# UVBoxSchematic_r.net
KiCad netlist of a schematic drawn in EAGLE
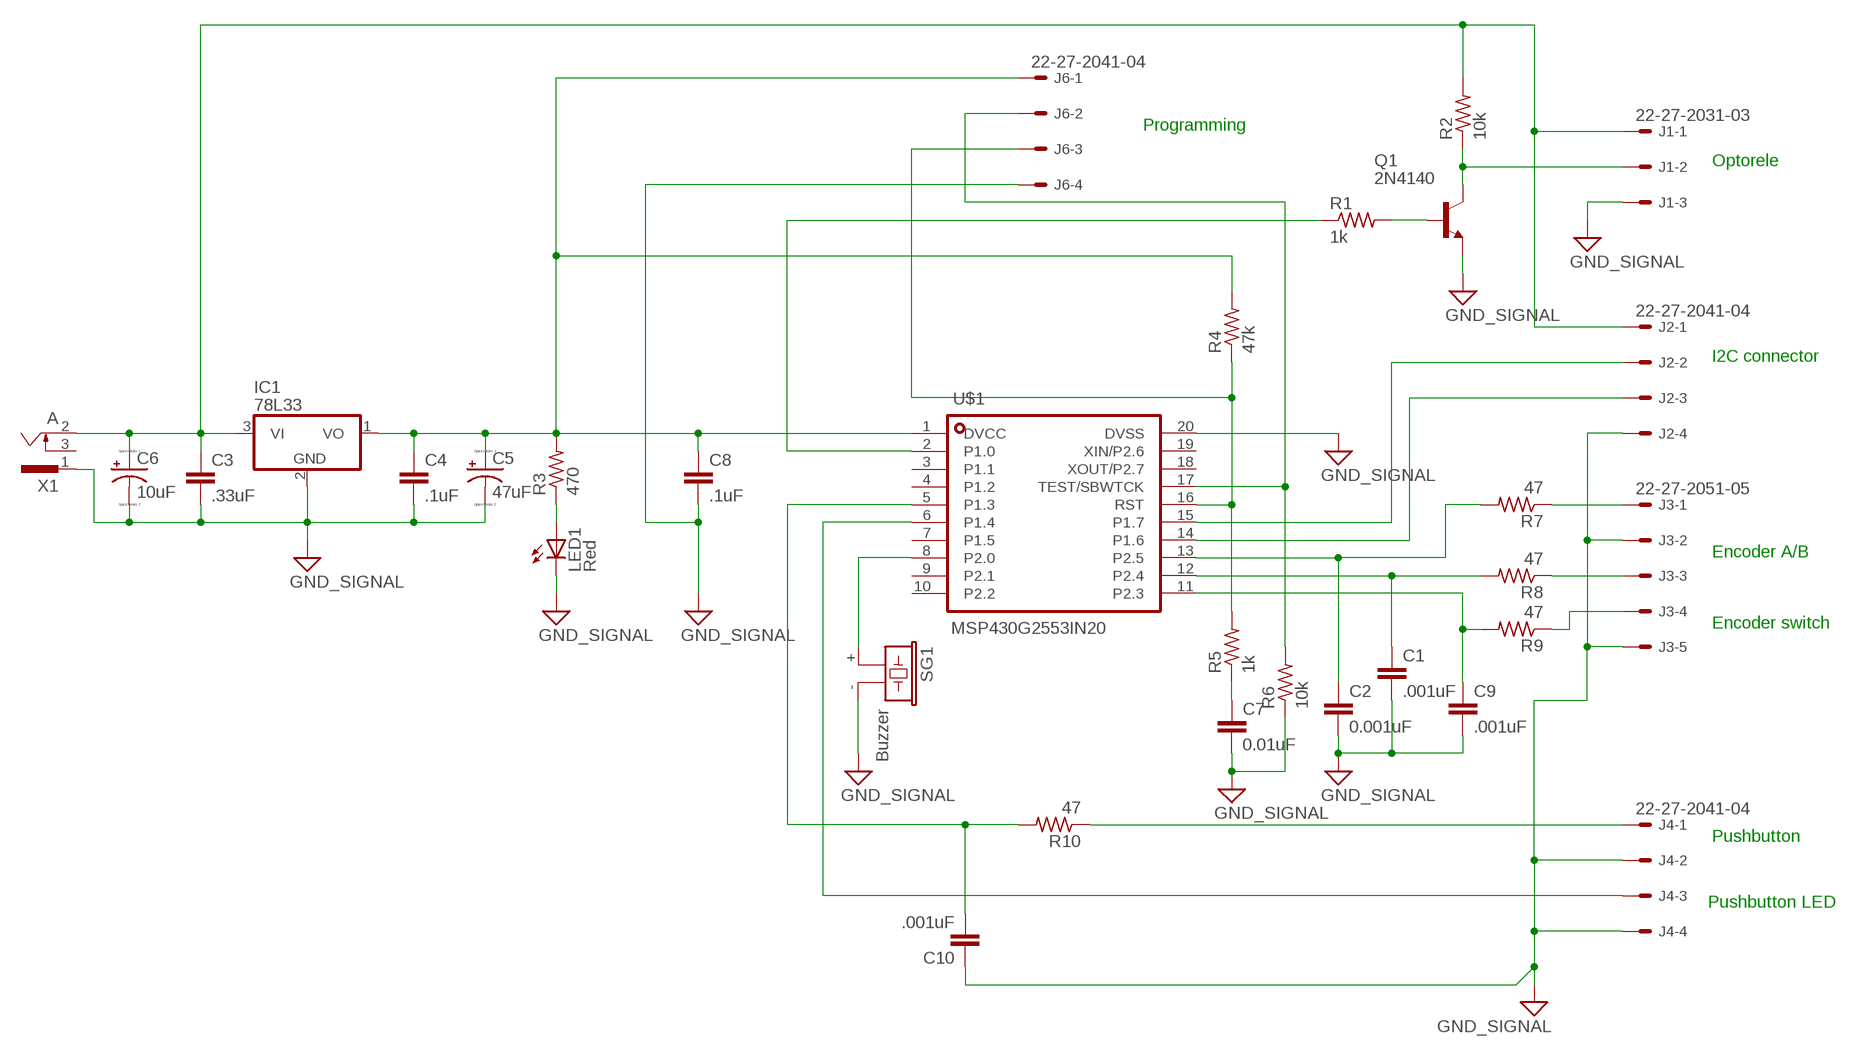
[diagram p0: schematic, sheet 1]

(export (version "E")
  (design (tool "Eeschema 10.0.6"))
  (components
    (comp (ref "C1")
      (value ".001uF")
      (footprint "eagle-import:C2.5-2")
      (libsource (lib "eagle-import") (part "C2.5/2"))
    )
    (comp (ref "C2")
      (value "0.001uF")
      (footprint "eagle-import:C2.5-2")
      (libsource (lib "eagle-import") (part "C2.5/2"))
    )
    (comp (ref "C3")
      (value ".33uF")
      (footprint "eagle-import:C2.5-2")
      (libsource (lib "eagle-import") (part "C2.5/2"))
    )
    (comp (ref "C4")
      (value ".1uF")
      (footprint "eagle-import:C2.5-2")
      (libsource (lib "eagle-import") (part "C2.5/2"))
    )
    (comp (ref "C5")
      (value "47uF")
      (footprint "eagle-import:B45181A")
      (libsource (lib "eagle-import") (part "CPOL-USB45181A"))
    )
    (comp (ref "C6")
      (value "10uF")
      (footprint "eagle-import:B45181A")
      (libsource (lib "eagle-import") (part "CPOL-USB45181A"))
    )
    (comp (ref "C7")
      (value "0.01uF")
      (footprint "eagle-import:C2.5-2")
      (libsource (lib "eagle-import") (part "C2.5/2"))
    )
    (comp (ref "C8")
      (value ".1uF")
      (footprint "eagle-import:C2.5-2")
      (libsource (lib "eagle-import") (part "C2.5/2"))
    )
    (comp (ref "C9")
      (value ".001uF")
      (footprint "eagle-import:C2.5-2")
      (libsource (lib "eagle-import") (part "C2.5/2"))
    )
    (comp (ref "C10")
      (value ".001uF")
      (footprint "eagle-import:C2.5-2")
      (libsource (lib "eagle-import") (part "C2.5/2"))
    )
    (comp (ref "IC1")
      (value "78L33")
      (footprint "eagle-import:TO92")
      (libsource (lib "eagle-import") (part "78ZL05"))
    )
    (comp (ref "J1")
      (value "22-27-2031-03")
      (footprint "eagle-import:6410-03")
      (libsource (lib "eagle-import") (part "22-?-0327-2031"))
    )
    (comp (ref "J2")
      (value "22-27-2041-04")
      (footprint "eagle-import:6410-04")
      (libsource (lib "eagle-import") (part "22-?-0427-2041"))
    )
    (comp (ref "J3")
      (value "22-27-2051-05")
      (footprint "eagle-import:6410-05")
      (libsource (lib "eagle-import") (part "22-?-0527-2051"))
    )
    (comp (ref "J4")
      (value "22-27-2041-04")
      (footprint "eagle-import:6410-04")
      (libsource (lib "eagle-import") (part "22-?-0427-2041"))
    )
    (comp (ref "J6")
      (value "22-27-2041-04")
      (footprint "eagle-import:6410-04")
      (libsource (lib "eagle-import") (part "22-?-0427-2041"))
    )
    (comp (ref "LED1")
      (value "Red")
      (footprint "eagle-import:LED3MM")
      (libsource (lib "eagle-import") (part "LED3MM"))
    )
    (comp (ref "Q1")
      (value "2N4140")
      (footprint "eagle-import:TO18")
      (libsource (lib "eagle-import") (part "2N4104"))
    )
    (comp (ref "R1")
      (value "1k")
      (footprint "eagle-import:0204_7")
      (libsource (lib "eagle-import") (part "R-US_0204/7"))
    )
    (comp (ref "R2")
      (value "10k")
      (footprint "eagle-import:0204_7")
      (libsource (lib "eagle-import") (part "R-US_0204/7"))
    )
    (comp (ref "R3")
      (value "470")
      (footprint "eagle-import:0204_7")
      (libsource (lib "eagle-import") (part "R-US_0204/7"))
    )
    (comp (ref "R4")
      (value "47k")
      (footprint "eagle-import:0204_7")
      (libsource (lib "eagle-import") (part "R-US_0204/7"))
    )
    (comp (ref "R5")
      (value "1k")
      (footprint "eagle-import:0204_7")
      (libsource (lib "eagle-import") (part "R-US_0204/7"))
    )
    (comp (ref "R6")
      (value "10k")
      (footprint "eagle-import:0204_7")
      (libsource (lib "eagle-import") (part "R-US_0204/7"))
    )
    (comp (ref "R7")
      (value "47")
      (footprint "eagle-import:0204_7")
      (libsource (lib "eagle-import") (part "R-US_0204/7"))
    )
    (comp (ref "R8")
      (value "47")
      (footprint "eagle-import:0204_7")
      (libsource (lib "eagle-import") (part "R-US_0204/7"))
    )
    (comp (ref "R9")
      (value "47")
      (footprint "eagle-import:0204_7")
      (libsource (lib "eagle-import") (part "R-US_0204/7"))
    )
    (comp (ref "R10")
      (value "47")
      (footprint "eagle-import:0204_7")
      (libsource (lib "eagle-import") (part "R-US_0204/7"))
    )
    (comp (ref "SG1")
      (value "Buzzer")
      (footprint "eagle-import:F_CM04P")
      (libsource (lib "eagle-import") (part "F/CM04P"))
    )
    (comp (ref "U$1")
      (value "MSP430G2553IN20")
      (footprint "eagle-import:DIP20")
      (libsource (lib "eagle-import") (part "MSP430G2553IN20"))
    )
    (comp (ref "X1")
      (value "A")
      (footprint "eagle-import:SCD-014-A")
      (libsource (lib "eagle-import") (part "SCD-014A"))
    )
  )
  (nets
    (net (code "1") (name "GND_SIGNAL") (class "Default")
      (node (ref "C1") (pin "2") (pinfunction "2_2") (pintype "passive"))
      (node (ref "C10") (pin "1") (pinfunction "1_1") (pintype "passive"))
      (node (ref "C2") (pin "2") (pinfunction "2_2") (pintype "passive"))
      (node (ref "C3") (pin "2") (pinfunction "2_2") (pintype "passive"))
      (node (ref "C4") (pin "2") (pinfunction "2_2") (pintype "passive"))
      (node (ref "C5") (pin "-") (pinfunction "-_-") (pintype "passive"))
      (node (ref "C6") (pin "-") (pinfunction "-_-") (pintype "passive"))
      (node (ref "C7") (pin "2") (pinfunction "2_2") (pintype "passive"))
      (node (ref "C8") (pin "2") (pinfunction "2_2") (pintype "passive"))
      (node (ref "C9") (pin "2") (pinfunction "2_2") (pintype "passive"))
      (node (ref "IC1") (pin "2") (pinfunction "GND_2") (pintype "passive"))
      (node (ref "J1") (pin "3") (pinfunction "S_3") (pintype "passive"))
      (node (ref "J2") (pin "4") (pinfunction "S_4") (pintype "passive"))
      (node (ref "J3") (pin "2") (pinfunction "S_2") (pintype "passive"))
      (node (ref "J3") (pin "5") (pinfunction "S_5") (pintype "passive"))
      (node (ref "J4") (pin "2") (pinfunction "S_2") (pintype "passive"))
      (node (ref "J4") (pin "4") (pinfunction "S_4") (pintype "passive"))
      (node (ref "J6") (pin "4") (pinfunction "S_4") (pintype "passive"))
      (node (ref "LED1") (pin "K") (pinfunction "C_K") (pintype "passive"))
      (node (ref "Q1") (pin "1") (pinfunction "E_1") (pintype "passive"))
      (node (ref "R6") (pin "1") (pinfunction "1_1") (pintype "passive"))
      (node (ref "SG1") (pin "-") (pinfunction "2_-") (pintype "passive"))
      (node (ref "U$1") (pin "20") (pinfunction "DVSS_20") (pintype "power_in"))
      (node (ref "X1") (pin "1") (pinfunction "1_1") (pintype "passive"))
    )
    (net (code "2") (name "Net-(C7-Pad1)") (class "Default")
      (node (ref "C7") (pin "1") (pinfunction "1_1") (pintype "passive"))
      (node (ref "R5") (pin "1") (pinfunction "1_1") (pintype "passive"))
    )
    (net (code "3") (name "Net-(IC1-VI)") (class "Default")
      (node (ref "C3") (pin "1") (pinfunction "1_1") (pintype "passive"))
      (node (ref "C6") (pin "+") (pinfunction "+_+") (pintype "passive"))
      (node (ref "IC1") (pin "3") (pinfunction "VI_3") (pintype "input"))
      (node (ref "J1") (pin "1") (pinfunction "S_1") (pintype "passive"))
      (node (ref "J2") (pin "1") (pinfunction "S_1") (pintype "passive"))
      (node (ref "R2") (pin "2") (pinfunction "2_2") (pintype "passive"))
      (node (ref "X1") (pin "2") (pinfunction "2_2") (pintype "passive"))
    )
    (net (code "4") (name "Net-(IC1-VO)") (class "Default")
      (node (ref "C4") (pin "1") (pinfunction "1_1") (pintype "passive"))
      (node (ref "C5") (pin "+") (pinfunction "+_+") (pintype "passive"))
      (node (ref "C8") (pin "1") (pinfunction "1_1") (pintype "passive"))
      (node (ref "IC1") (pin "1") (pinfunction "VO_1") (pintype "passive"))
      (node (ref "J6") (pin "1") (pinfunction "S_1") (pintype "passive"))
      (node (ref "R3") (pin "2") (pinfunction "2_2") (pintype "passive"))
      (node (ref "R4") (pin "2") (pinfunction "2_2") (pintype "passive"))
      (node (ref "U$1") (pin "1") (pinfunction "DVCC_1") (pintype "power_in"))
    )
    (net (code "5") (name "Net-(J1B-S)") (class "Default")
      (node (ref "J1") (pin "2") (pinfunction "S_2") (pintype "passive"))
      (node (ref "Q1") (pin "3") (pinfunction "C_3") (pintype "passive"))
      (node (ref "R2") (pin "1") (pinfunction "1_1") (pintype "passive"))
    )
    (net (code "6") (name "Net-(J2B-S)") (class "Default")
      (node (ref "J2") (pin "2") (pinfunction "S_2") (pintype "passive"))
      (node (ref "U$1") (pin "15") (pinfunction "P1.7_15") (pintype "bidirectional"))
    )
    (net (code "7") (name "Net-(J2C-S)") (class "Default")
      (node (ref "J2") (pin "3") (pinfunction "S_3") (pintype "passive"))
      (node (ref "U$1") (pin "14") (pinfunction "P1.6_14") (pintype "bidirectional"))
    )
    (net (code "8") (name "Net-(J3A-S)") (class "Default")
      (node (ref "J3") (pin "1") (pinfunction "S_1") (pintype "passive"))
      (node (ref "R7") (pin "1") (pinfunction "1_1") (pintype "passive"))
    )
    (net (code "9") (name "Net-(J3C-S)") (class "Default")
      (node (ref "J3") (pin "3") (pinfunction "S_3") (pintype "passive"))
      (node (ref "R8") (pin "1") (pinfunction "1_1") (pintype "passive"))
    )
    (net (code "10") (name "Net-(J3D-S)") (class "Default")
      (node (ref "J3") (pin "4") (pinfunction "S_4") (pintype "passive"))
      (node (ref "R9") (pin "1") (pinfunction "1_1") (pintype "passive"))
    )
    (net (code "11") (name "Net-(J4A-S)") (class "Default")
      (node (ref "J4") (pin "1") (pinfunction "S_1") (pintype "passive"))
      (node (ref "R10") (pin "1") (pinfunction "1_1") (pintype "passive"))
    )
    (net (code "12") (name "Net-(J4C-S)") (class "Default")
      (node (ref "J4") (pin "3") (pinfunction "S_3") (pintype "passive"))
      (node (ref "U$1") (pin "6") (pinfunction "P1.4_6") (pintype "bidirectional"))
    )
    (net (code "13") (name "Net-(J6B-S)") (class "Default")
      (node (ref "J6") (pin "2") (pinfunction "S_2") (pintype "passive"))
      (node (ref "R6") (pin "2") (pinfunction "2_2") (pintype "passive"))
      (node (ref "U$1") (pin "17") (pinfunction "TEST/SBWTCK_17") (pintype "bidirectional"))
    )
    (net (code "14") (name "Net-(J6C-S)") (class "Default")
      (node (ref "J6") (pin "3") (pinfunction "S_3") (pintype "passive"))
      (node (ref "R4") (pin "1") (pinfunction "1_1") (pintype "passive"))
      (node (ref "R5") (pin "2") (pinfunction "2_2") (pintype "passive"))
      (node (ref "U$1") (pin "16") (pinfunction "RST_16") (pintype "bidirectional"))
    )
    (net (code "15") (name "Net-(LED1-PadA)") (class "Default")
      (node (ref "LED1") (pin "A") (pinfunction "A_A") (pintype "passive"))
      (node (ref "R3") (pin "1") (pinfunction "1_1") (pintype "passive"))
    )
    (net (code "16") (name "Net-(Q1-B)") (class "Default")
      (node (ref "Q1") (pin "2") (pinfunction "B_2") (pintype "passive"))
      (node (ref "R1") (pin "2") (pinfunction "2_2") (pintype "passive"))
    )
    (net (code "17") (name "Net-(SG1-1)") (class "Default")
      (node (ref "SG1") (pin "+") (pinfunction "1_+") (pintype "passive"))
      (node (ref "U$1") (pin "8") (pinfunction "P2.0_8") (pintype "bidirectional"))
    )
    (net (code "18") (name "Net-(U$1-P1.0)") (class "Default")
      (node (ref "R1") (pin "1") (pinfunction "1_1") (pintype "passive"))
      (node (ref "U$1") (pin "2") (pinfunction "P1.0_2") (pintype "bidirectional"))
    )
    (net (code "19") (name "Net-(U$1-P1.3)") (class "Default")
      (node (ref "C10") (pin "2") (pinfunction "2_2") (pintype "passive"))
      (node (ref "R10") (pin "2") (pinfunction "2_2") (pintype "passive"))
      (node (ref "U$1") (pin "5") (pinfunction "P1.3_5") (pintype "bidirectional"))
    )
    (net (code "20") (name "Net-(U$1-P2.3)") (class "Default")
      (node (ref "C9") (pin "1") (pinfunction "1_1") (pintype "passive"))
      (node (ref "R9") (pin "2") (pinfunction "2_2") (pintype "passive"))
      (node (ref "U$1") (pin "11") (pinfunction "P2.3_11") (pintype "bidirectional"))
    )
    (net (code "21") (name "Net-(U$1-P2.4)") (class "Default")
      (node (ref "C1") (pin "1") (pinfunction "1_1") (pintype "passive"))
      (node (ref "R8") (pin "2") (pinfunction "2_2") (pintype "passive"))
      (node (ref "U$1") (pin "12") (pinfunction "P2.4_12") (pintype "bidirectional"))
    )
    (net (code "22") (name "Net-(U$1-P2.5)") (class "Default")
      (node (ref "C2") (pin "1") (pinfunction "1_1") (pintype "passive"))
      (node (ref "R7") (pin "2") (pinfunction "2_2") (pintype "passive"))
      (node (ref "U$1") (pin "13") (pinfunction "P2.5_13") (pintype "bidirectional"))
    )
    (net (code "23") (name "unconnected-(U$1-P1.1-Pad3)") (class "Default")
      (node (ref "U$1") (pin "3") (pinfunction "P1.1_3") (pintype "bidirectional"))
    )
    (net (code "24") (name "unconnected-(U$1-P1.2-Pad4)") (class "Default")
      (node (ref "U$1") (pin "4") (pinfunction "P1.2_4") (pintype "bidirectional"))
    )
    (net (code "25") (name "unconnected-(U$1-P1.5-Pad7)") (class "Default")
      (node (ref "U$1") (pin "7") (pinfunction "P1.5_7") (pintype "bidirectional"))
    )
    (net (code "26") (name "unconnected-(U$1-P2.1-Pad9)") (class "Default")
      (node (ref "U$1") (pin "9") (pinfunction "P2.1_9") (pintype "bidirectional"))
    )
    (net (code "27") (name "unconnected-(U$1-P2.2-Pad10)") (class "Default")
      (node (ref "U$1") (pin "10") (pinfunction "P2.2_10") (pintype "bidirectional"))
    )
    (net (code "28") (name "unconnected-(U$1-XIN{slash}P2.6-Pad19)") (class "Default")
      (node (ref "U$1") (pin "19") (pinfunction "XIN/P2.6_19") (pintype "bidirectional"))
    )
    (net (code "29") (name "unconnected-(U$1-XOUT{slash}P2.7-Pad18)") (class "Default")
      (node (ref "U$1") (pin "18") (pinfunction "XOUT/P2.7_18") (pintype "bidirectional"))
    )
    (net (code "30") (name "unconnected-(X1-Pad3)") (class "Default")
      (node (ref "X1") (pin "3") (pinfunction "3_3") (pintype "passive"))
    )
  )
)
